# Sheet1.net
KiCad netlist of a schematic drawn in Altium Designer
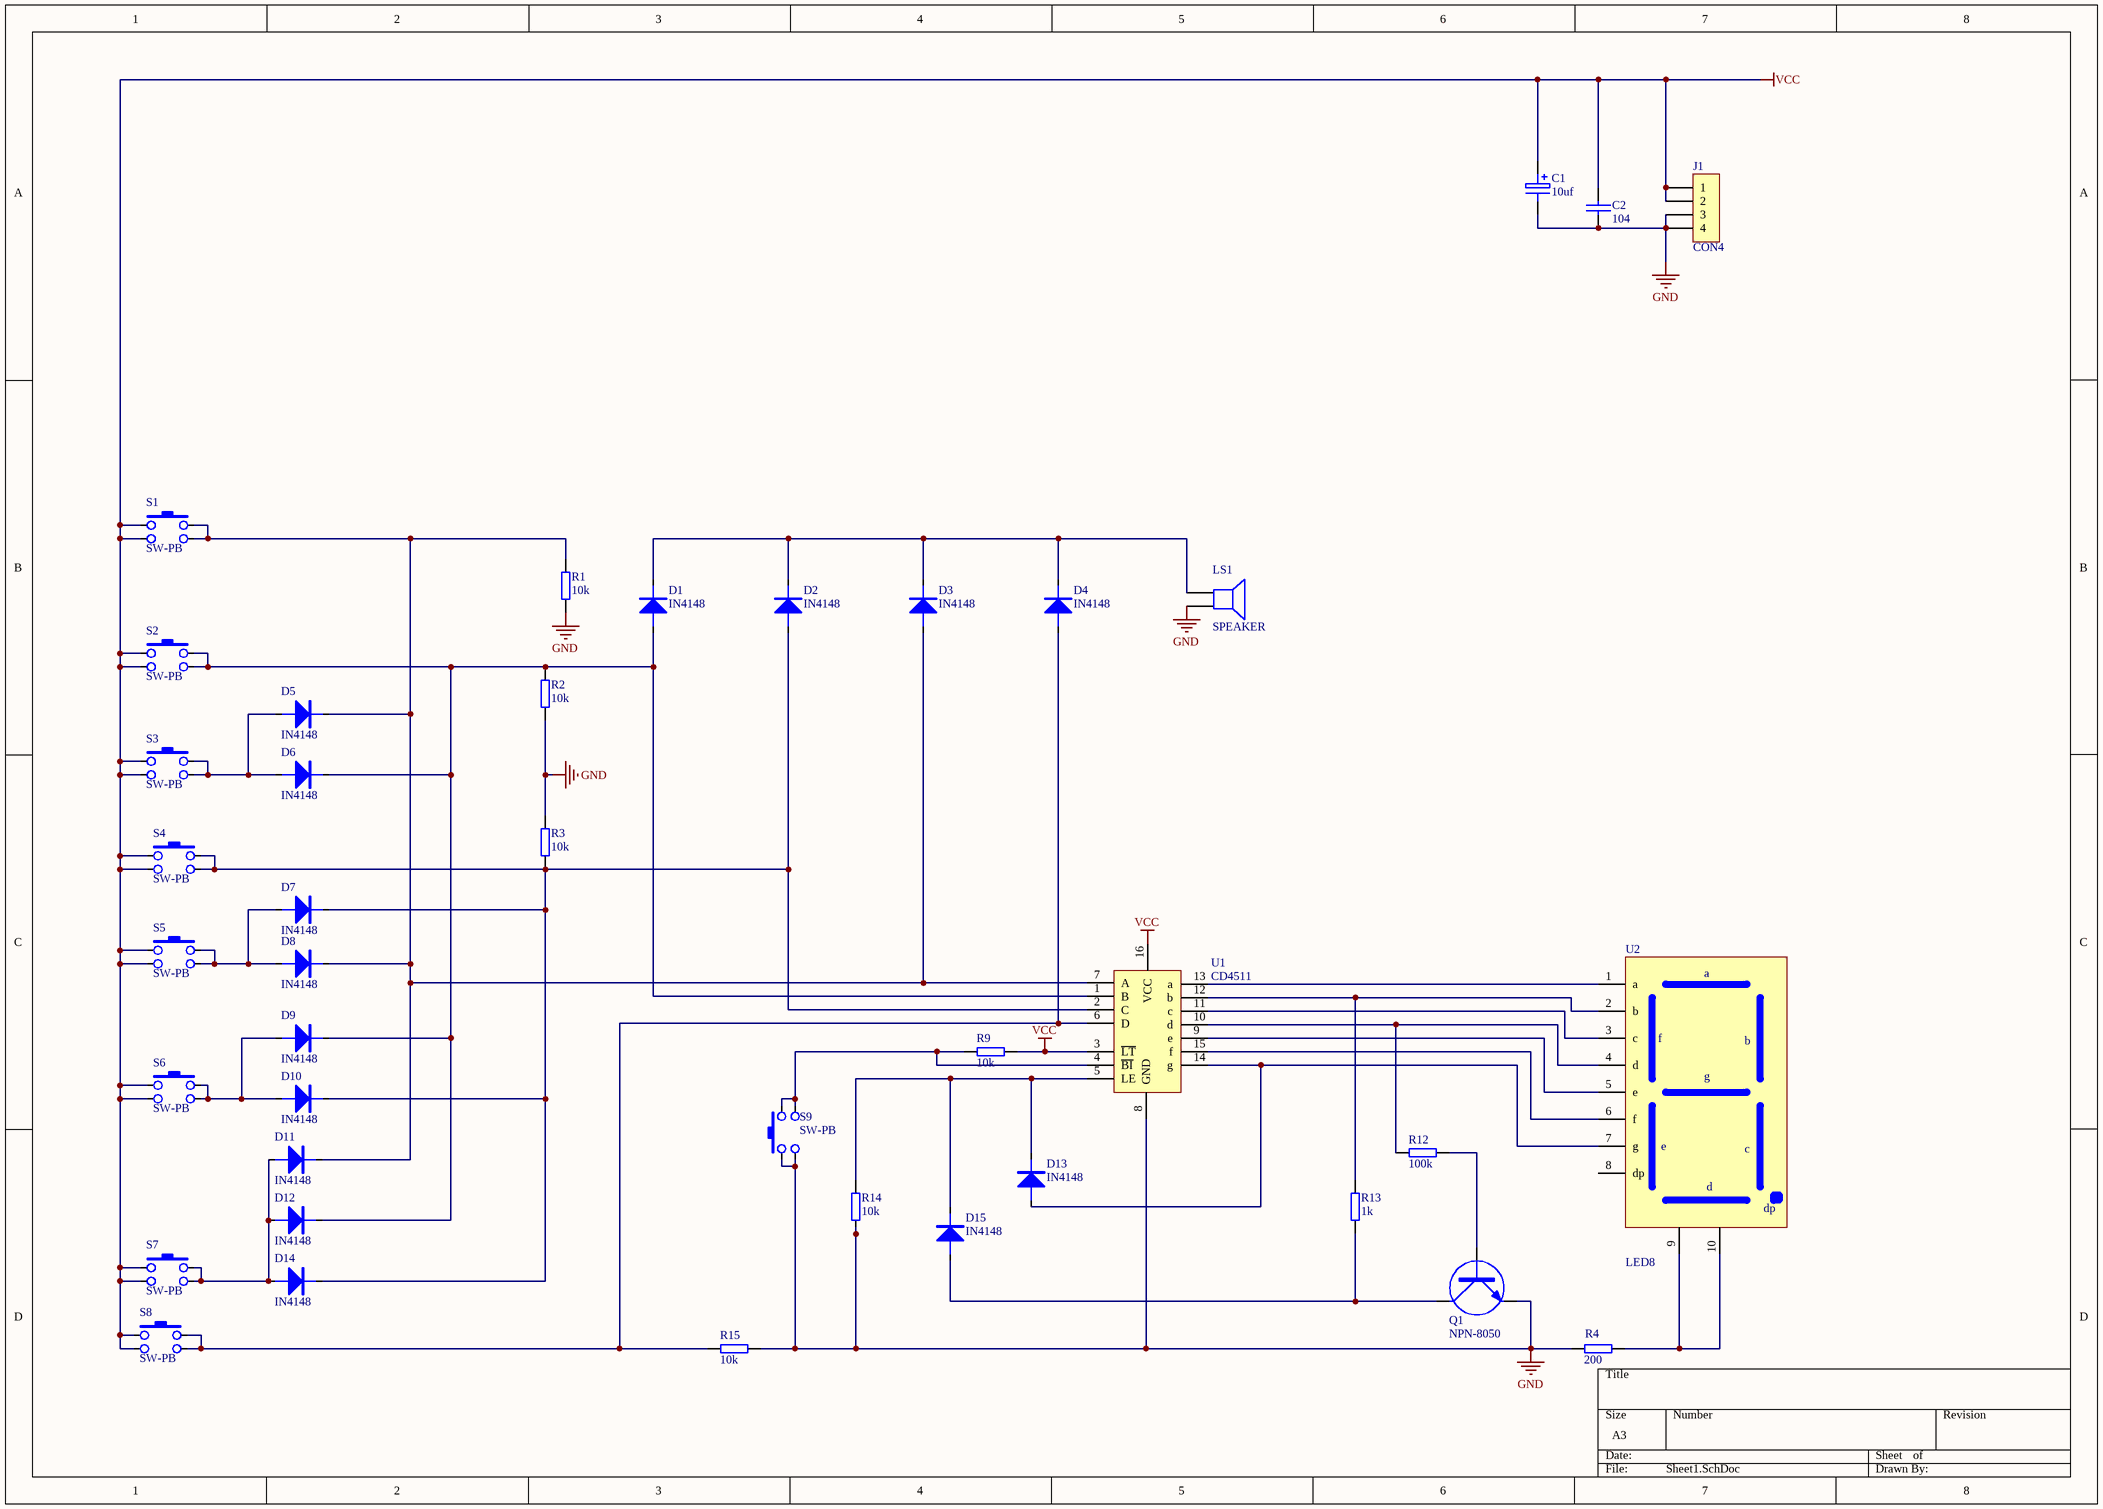
[diagram p0: Sheet1.SchDoc]

(export (version "E")
  (design (tool "Eeschema 10.0.6"))
  (components
    (comp (ref "C1")
      (value "10uf")
      (footprint "RB.1/.2")
      (description "Electrolytic Capacitor")
      (libsource (lib "8路抢答器电路设计") (part "ELECTRO1"))
    )
    (comp (ref "C2")
      (value "104")
      (footprint "RAD0.1")
      (description "Capacitor")
      (libsource (lib "8路抢答器电路设计") (part "CAP"))
    )
    (comp (ref "D1") (value "IN4148") (footprint "DIODE0.3") (libsource (lib "8路抢答器电路设计") (part "DIODE")))
    (comp (ref "D2") (value "IN4148") (footprint "DIODE0.3") (libsource (lib "8路抢答器电路设计") (part "DIODE")))
    (comp (ref "D3") (value "IN4148") (footprint "DIODE0.3") (libsource (lib "8路抢答器电路设计") (part "DIODE")))
    (comp (ref "D4") (value "IN4148") (footprint "DIODE0.3") (libsource (lib "8路抢答器电路设计") (part "DIODE")))
    (comp (ref "D5") (value "IN4148") (footprint "DIODE0.3") (libsource (lib "8路抢答器电路设计") (part "DIODE")))
    (comp (ref "D6") (value "IN4148") (footprint "DIODE0.3") (libsource (lib "8路抢答器电路设计") (part "DIODE")))
    (comp (ref "D7") (value "IN4148") (footprint "DIODE0.3") (libsource (lib "8路抢答器电路设计") (part "DIODE")))
    (comp (ref "D8") (value "IN4148") (footprint "DIODE0.3") (libsource (lib "8路抢答器电路设计") (part "DIODE")))
    (comp (ref "D9") (value "IN4148") (footprint "DIODE0.3") (libsource (lib "8路抢答器电路设计") (part "DIODE")))
    (comp (ref "D10") (value "IN4148") (footprint "DIODE0.3") (libsource (lib "8路抢答器电路设计") (part "DIODE")))
    (comp (ref "D11") (value "IN4148") (footprint "DIODE0.3") (libsource (lib "8路抢答器电路设计") (part "DIODE")))
    (comp (ref "D12") (value "IN4148") (footprint "DIODE0.3") (libsource (lib "8路抢答器电路设计") (part "DIODE")))
    (comp (ref "D13") (value "IN4148") (footprint "DIODE0.3") (libsource (lib "8路抢答器电路设计") (part "DIODE")))
    (comp (ref "D14") (value "IN4148") (footprint "DIODE0.3") (libsource (lib "8路抢答器电路设计") (part "DIODE")))
    (comp (ref "D15") (value "IN4148") (footprint "DIODE0.3") (libsource (lib "8路抢答器电路设计") (part "DIODE")))
    (comp (ref "J1")
      (value "CON4")
      (footprint "SIP4")
      (description "Connector")
      (libsource (lib "8路抢答器电路设计") (part "CON4"))
    )
    (comp (ref "LS1") (value "SPEAKER") (footprint "H") (libsource (lib "8路抢答器电路设计") (part "SPEAKER")))
    (comp (ref "Q1") (value "NPN-8050") (footprint "TO-92C") (libsource (lib "8路抢答器电路设计") (part "NPN")))
    (comp (ref "R1") (value "10k") (footprint "AXIAL0.3") (libsource (lib "8路抢答器电路设计") (part "RES2")))
    (comp (ref "R2") (value "10k") (footprint "AXIAL0.3") (libsource (lib "8路抢答器电路设计") (part "RES2")))
    (comp (ref "R3") (value "10k") (footprint "AXIAL0.3") (libsource (lib "8路抢答器电路设计") (part "RES2")))
    (comp (ref "R4") (value "200") (footprint "AXIAL0.3") (libsource (lib "8路抢答器电路设计") (part "RES2")))
    (comp (ref "R9") (value "10k") (footprint "AXIAL0.3") (libsource (lib "8路抢答器电路设计") (part "RES2")))
    (comp (ref "R12") (value "100k") (footprint "AXIAL0.3") (libsource (lib "8路抢答器电路设计") (part "RES2")))
    (comp (ref "R13") (value "1k") (footprint "AXIAL0.3") (libsource (lib "8路抢答器电路设计") (part "RES2")))
    (comp (ref "R14") (value "10k") (footprint "AXIAL0.3") (libsource (lib "8路抢答器电路设计") (part "RES2")))
    (comp (ref "R15") (value "10k") (footprint "AXIAL0.3") (libsource (lib "8路抢答器电路设计") (part "RES2")))
    (comp (ref "S1") (value "SW-PB") (footprint "SWPB") (libsource (lib "8路抢答器电路设计") (part "SW-PB")))
    (comp (ref "S2") (value "SW-PB") (footprint "SWPB") (libsource (lib "8路抢答器电路设计") (part "SW-PB")))
    (comp (ref "S3") (value "SW-PB") (footprint "SWPB") (libsource (lib "8路抢答器电路设计") (part "SW-PB")))
    (comp (ref "S4") (value "SW-PB") (footprint "SWPB") (libsource (lib "8路抢答器电路设计") (part "SW-PB")))
    (comp (ref "S5") (value "SW-PB") (footprint "SWPB") (libsource (lib "8路抢答器电路设计") (part "SW-PB")))
    (comp (ref "S6") (value "SW-PB") (footprint "SWPB") (libsource (lib "8路抢答器电路设计") (part "SW-PB")))
    (comp (ref "S7") (value "SW-PB") (footprint "SWPB") (libsource (lib "8路抢答器电路设计") (part "SW-PB")))
    (comp (ref "S8") (value "SW-PB") (footprint "SWPB") (libsource (lib "8路抢答器电路设计") (part "SW-PB")))
    (comp (ref "S9") (value "SW-PB") (footprint "SWPB") (libsource (lib "8路抢答器电路设计") (part "SW-PB")))
    (comp (ref "U1") (value "CD4511") (footprint "DIP16") (libsource (lib "Schlib1") (part "CD4511")))
    (comp (ref "U2") (value "LED8") (footprint "LED8") (libsource (lib "8路抢答器电路设计") (part "LED8")))
  )
  (nets
    (net (code "1") (name "GND") (class "Default")
      (node (ref "C1") (pin "2") (pinfunction "2_2") (pintype "passive"))
      (node (ref "C2") (pin "2") (pinfunction "2_2") (pintype "passive"))
      (node (ref "J1") (pin "3") (pinfunction "3_3") (pintype "passive"))
      (node (ref "J1") (pin "4") (pinfunction "4_4") (pintype "passive"))
      (node (ref "LS1") (pin "2") (pinfunction "2_2") (pintype "passive"))
      (node (ref "Q1") (pin "E") (pinfunction "E_E") (pintype "passive"))
      (node (ref "R1") (pin "1") (pinfunction "1_1") (pintype "passive"))
      (node (ref "R14") (pin "1") (pinfunction "1_1") (pintype "passive"))
      (node (ref "R15") (pin "2") (pinfunction "2_2") (pintype "passive"))
      (node (ref "R2") (pin "1") (pinfunction "1_1") (pintype "passive"))
      (node (ref "R3") (pin "2") (pinfunction "2_2") (pintype "passive"))
      (node (ref "R4") (pin "1") (pinfunction "1_1") (pintype "passive"))
      (node (ref "S9") (pin "1") (pinfunction "1_1") (pintype "passive"))
      (node (ref "S9") (pin "3") (pinfunction "3_3") (pintype "passive"))
      (node (ref "U1") (pin "8") (pinfunction "GND_8") (pintype "passive"))
    )
    (net (code "2") (name "Net-(D1-PadK)") (class "Default")
      (node (ref "D1") (pin "K") (pinfunction "K_K") (pintype "passive"))
      (node (ref "D2") (pin "K") (pinfunction "K_K") (pintype "passive"))
      (node (ref "D3") (pin "K") (pinfunction "K_K") (pintype "passive"))
      (node (ref "D4") (pin "K") (pinfunction "K_K") (pintype "passive"))
      (node (ref "LS1") (pin "1") (pinfunction "1_1") (pintype "passive"))
    )
    (net (code "3") (name "Net-(D5-PadA)") (class "Default")
      (node (ref "D5") (pin "A") (pinfunction "A_A") (pintype "passive"))
      (node (ref "D6") (pin "A") (pinfunction "A_A") (pintype "passive"))
      (node (ref "S3") (pin "2") (pinfunction "2_2") (pintype "passive"))
      (node (ref "S3") (pin "4") (pinfunction "4_4") (pintype "passive"))
    )
    (net (code "4") (name "Net-(D7-PadA)") (class "Default")
      (node (ref "D7") (pin "A") (pinfunction "A_A") (pintype "passive"))
      (node (ref "D8") (pin "A") (pinfunction "A_A") (pintype "passive"))
      (node (ref "S5") (pin "2") (pinfunction "2_2") (pintype "passive"))
      (node (ref "S5") (pin "4") (pinfunction "4_4") (pintype "passive"))
    )
    (net (code "5") (name "Net-(D10-PadA)") (class "Default")
      (node (ref "D10") (pin "A") (pinfunction "A_A") (pintype "passive"))
      (node (ref "D9") (pin "A") (pinfunction "A_A") (pintype "passive"))
      (node (ref "S6") (pin "2") (pinfunction "2_2") (pintype "passive"))
      (node (ref "S6") (pin "4") (pinfunction "4_4") (pintype "passive"))
    )
    (net (code "6") (name "Net-(D11-PadA)") (class "Default")
      (node (ref "D11") (pin "A") (pinfunction "A_A") (pintype "passive"))
      (node (ref "D12") (pin "A") (pinfunction "A_A") (pintype "passive"))
      (node (ref "D14") (pin "A") (pinfunction "A_A") (pintype "passive"))
      (node (ref "S7") (pin "2") (pinfunction "2_2") (pintype "passive"))
      (node (ref "S7") (pin "4") (pinfunction "4_4") (pintype "passive"))
    )
    (net (code "7") (name "Net-(D15-PadA)") (class "Default")
      (node (ref "D15") (pin "A") (pinfunction "A_A") (pintype "passive"))
      (node (ref "Q1") (pin "C") (pinfunction "C_C") (pintype "passive"))
      (node (ref "R13") (pin "1") (pinfunction "1_1") (pintype "passive"))
    )
    (net (code "8") (name "Net-(Q1-PadB)") (class "Default")
      (node (ref "Q1") (pin "B") (pinfunction "B_B") (pintype "passive"))
      (node (ref "R12") (pin "2") (pinfunction "2_2") (pintype "passive"))
    )
    (net (code "9") (name "Net-(R4-Pad2)") (class "Default")
      (node (ref "R4") (pin "2") (pinfunction "2_2") (pintype "passive"))
      (node (ref "U2") (pin "10") (pinfunction "COM_10") (pintype "passive"))
      (node (ref "U2") (pin "9") (pinfunction "COM_9") (pintype "passive"))
    )
    (net (code "10") (name "Net-(U1-A)") (class "Default")
      (node (ref "D11") (pin "K") (pinfunction "K_K") (pintype "passive"))
      (node (ref "D3") (pin "A") (pinfunction "A_A") (pintype "passive"))
      (node (ref "D5") (pin "K") (pinfunction "K_K") (pintype "passive"))
      (node (ref "D8") (pin "K") (pinfunction "K_K") (pintype "passive"))
      (node (ref "R1") (pin "2") (pinfunction "2_2") (pintype "passive"))
      (node (ref "S1") (pin "2") (pinfunction "2_2") (pintype "passive"))
      (node (ref "S1") (pin "4") (pinfunction "4_4") (pintype "passive"))
      (node (ref "U1") (pin "7") (pinfunction "A_7") (pintype "passive"))
    )
    (net (code "11") (name "Net-(U1-B)") (class "Default")
      (node (ref "D1") (pin "A") (pinfunction "A_A") (pintype "passive"))
      (node (ref "D12") (pin "K") (pinfunction "K_K") (pintype "passive"))
      (node (ref "D6") (pin "K") (pinfunction "K_K") (pintype "passive"))
      (node (ref "D9") (pin "K") (pinfunction "K_K") (pintype "passive"))
      (node (ref "R2") (pin "2") (pinfunction "2_2") (pintype "passive"))
      (node (ref "S2") (pin "2") (pinfunction "2_2") (pintype "passive"))
      (node (ref "S2") (pin "4") (pinfunction "4_4") (pintype "passive"))
      (node (ref "U1") (pin "1") (pinfunction "B_1") (pintype "passive"))
    )
    (net (code "12") (name "Net-(U1-C)") (class "Default")
      (node (ref "D10") (pin "K") (pinfunction "K_K") (pintype "passive"))
      (node (ref "D14") (pin "K") (pinfunction "K_K") (pintype "passive"))
      (node (ref "D2") (pin "A") (pinfunction "A_A") (pintype "passive"))
      (node (ref "D7") (pin "K") (pinfunction "K_K") (pintype "passive"))
      (node (ref "R3") (pin "1") (pinfunction "1_1") (pintype "passive"))
      (node (ref "S4") (pin "2") (pinfunction "2_2") (pintype "passive"))
      (node (ref "S4") (pin "4") (pinfunction "4_4") (pintype "passive"))
      (node (ref "U1") (pin "2") (pinfunction "C_2") (pintype "passive"))
    )
    (net (code "13") (name "Net-(U1-D)") (class "Default")
      (node (ref "D4") (pin "A") (pinfunction "A_A") (pintype "passive"))
      (node (ref "R15") (pin "1") (pinfunction "1_1") (pintype "passive"))
      (node (ref "S8") (pin "2") (pinfunction "2_2") (pintype "passive"))
      (node (ref "S8") (pin "4") (pinfunction "4_4") (pintype "passive"))
      (node (ref "U1") (pin "6") (pinfunction "D_6") (pintype "passive"))
    )
    (net (code "14") (name "Net-(U1-LE)") (class "Default")
      (node (ref "D13") (pin "K") (pinfunction "K_K") (pintype "passive"))
      (node (ref "D15") (pin "K") (pinfunction "K_K") (pintype "passive"))
      (node (ref "R14") (pin "2") (pinfunction "2_2") (pintype "passive"))
      (node (ref "U1") (pin "5") (pinfunction "LE_5") (pintype "passive"))
    )
    (net (code "15") (name "Net-(U1-a)") (class "Default")
      (node (ref "U1") (pin "13") (pinfunction "a_13") (pintype "passive"))
      (node (ref "U2") (pin "1") (pinfunction "a_1") (pintype "passive"))
    )
    (net (code "16") (name "Net-(U1-b)") (class "Default")
      (node (ref "R13") (pin "2") (pinfunction "2_2") (pintype "passive"))
      (node (ref "U1") (pin "12") (pinfunction "b_12") (pintype "passive"))
      (node (ref "U2") (pin "2") (pinfunction "b_2") (pintype "passive"))
    )
    (net (code "17") (name "Net-(U1-c)") (class "Default")
      (node (ref "U1") (pin "11") (pinfunction "c_11") (pintype "passive"))
      (node (ref "U2") (pin "3") (pinfunction "c_3") (pintype "passive"))
    )
    (net (code "18") (name "Net-(U1-d)") (class "Default")
      (node (ref "R12") (pin "1") (pinfunction "1_1") (pintype "passive"))
      (node (ref "U1") (pin "10") (pinfunction "d_10") (pintype "passive"))
      (node (ref "U2") (pin "4") (pinfunction "d_4") (pintype "passive"))
    )
    (net (code "19") (name "Net-(U1-e)") (class "Default")
      (node (ref "U1") (pin "9") (pinfunction "e_9") (pintype "passive"))
      (node (ref "U2") (pin "5") (pinfunction "e_5") (pintype "passive"))
    )
    (net (code "20") (name "Net-(U1-f)") (class "Default")
      (node (ref "U1") (pin "15") (pinfunction "f_15") (pintype "passive"))
      (node (ref "U2") (pin "6") (pinfunction "f_6") (pintype "passive"))
    )
    (net (code "21") (name "Net-(U1-g)") (class "Default")
      (node (ref "D13") (pin "A") (pinfunction "A_A") (pintype "passive"))
      (node (ref "U1") (pin "14") (pinfunction "g_14") (pintype "passive"))
      (node (ref "U2") (pin "7") (pinfunction "g_7") (pintype "passive"))
    )
    (net (code "22") (name "Net-(U1-~{BI})") (class "Default")
      (node (ref "R9") (pin "1") (pinfunction "1_1") (pintype "passive"))
      (node (ref "S9") (pin "2") (pinfunction "2_2") (pintype "passive"))
      (node (ref "S9") (pin "4") (pinfunction "4_4") (pintype "passive"))
      (node (ref "U1") (pin "4") (pinfunction "~{BI}_4") (pintype "passive"))
    )
    (net (code "23") (name "VCC") (class "Default")
      (node (ref "C1") (pin "1") (pinfunction "1_1") (pintype "passive"))
      (node (ref "C2") (pin "1") (pinfunction "1_1") (pintype "passive"))
      (node (ref "J1") (pin "1") (pinfunction "1_1") (pintype "passive"))
      (node (ref "J1") (pin "2") (pinfunction "2_2") (pintype "passive"))
      (node (ref "R9") (pin "2") (pinfunction "2_2") (pintype "passive"))
      (node (ref "S1") (pin "1") (pinfunction "1_1") (pintype "passive"))
      (node (ref "S1") (pin "3") (pinfunction "3_3") (pintype "passive"))
      (node (ref "S2") (pin "1") (pinfunction "1_1") (pintype "passive"))
      (node (ref "S2") (pin "3") (pinfunction "3_3") (pintype "passive"))
      (node (ref "S3") (pin "1") (pinfunction "1_1") (pintype "passive"))
      (node (ref "S3") (pin "3") (pinfunction "3_3") (pintype "passive"))
      (node (ref "S4") (pin "1") (pinfunction "1_1") (pintype "passive"))
      (node (ref "S4") (pin "3") (pinfunction "3_3") (pintype "passive"))
      (node (ref "S5") (pin "1") (pinfunction "1_1") (pintype "passive"))
      (node (ref "S5") (pin "3") (pinfunction "3_3") (pintype "passive"))
      (node (ref "S6") (pin "1") (pinfunction "1_1") (pintype "passive"))
      (node (ref "S6") (pin "3") (pinfunction "3_3") (pintype "passive"))
      (node (ref "S7") (pin "1") (pinfunction "1_1") (pintype "passive"))
      (node (ref "S7") (pin "3") (pinfunction "3_3") (pintype "passive"))
      (node (ref "S8") (pin "1") (pinfunction "1_1") (pintype "passive"))
      (node (ref "S8") (pin "3") (pinfunction "3_3") (pintype "passive"))
      (node (ref "U1") (pin "16") (pinfunction "VCC_16") (pintype "passive"))
      (node (ref "U1") (pin "3") (pinfunction "~{LT}_3") (pintype "passive"))
    )
    (net (code "24") (name "unconnected-(U2-dp-Pad8)") (class "Default")
      (node (ref "U2") (pin "8") (pinfunction "dp_8") (pintype "passive"))
    )
  )
)
